# numitron-driver-v001.net
KiCad netlist of a schematic drawn in EAGLE
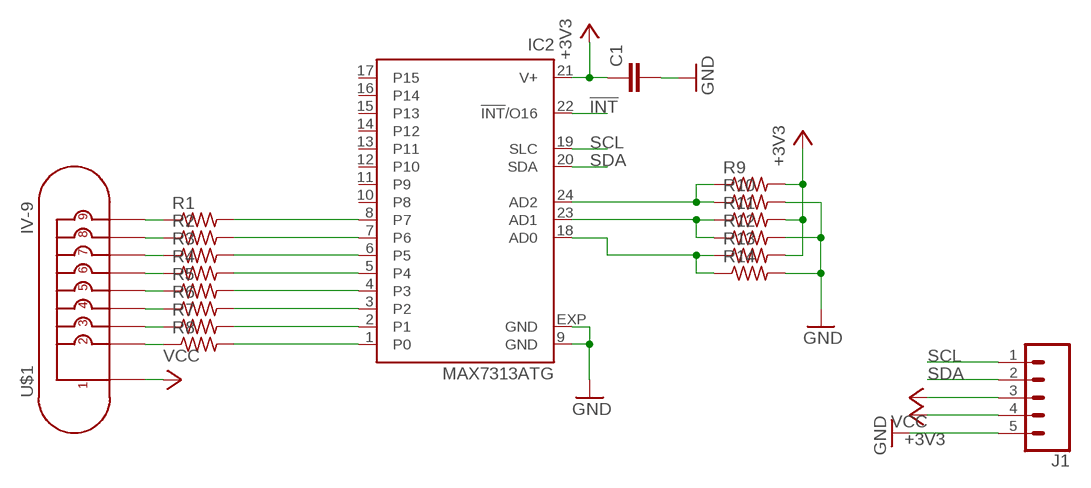
[diagram p0: schematic, sheet 1]

(export (version "E")
  (design (tool "Eeschema 10.0.6"))
  (components
    (comp (ref "C1")
      (value "C-EUC0603")
      (footprint "eagle-import:C0603")
      (libsource (lib "eagle-import") (part "C-EUC0603"))
    )
    (comp (ref "IC2")
      (value "MAX7313ATG")
      (footprint "eagle-import:TQFN24-EP")
      (fields (field (name "MF") "MAXIM"))
      (libsource (lib "eagle-import") (part "MAX7313ATG"))
    )
    (comp (ref "J1")
      (value "CONN_05NO_SILK")
      (footprint "eagle-import:1X05_NO_SILK")
      (libsource (lib "eagle-import") (part "CONN_05NO_SILK"))
    )
    (comp (ref "R1")
      (value "R-US_R0603")
      (footprint "eagle-import:R0603")
      (libsource (lib "eagle-import") (part "R-US_R0603"))
    )
    (comp (ref "R2")
      (value "R-US_R0603")
      (footprint "eagle-import:R0603")
      (libsource (lib "eagle-import") (part "R-US_R0603"))
    )
    (comp (ref "R3")
      (value "R-US_R0603")
      (footprint "eagle-import:R0603")
      (libsource (lib "eagle-import") (part "R-US_R0603"))
    )
    (comp (ref "R4")
      (value "R-US_R0603")
      (footprint "eagle-import:R0603")
      (libsource (lib "eagle-import") (part "R-US_R0603"))
    )
    (comp (ref "R5")
      (value "R-US_R0603")
      (footprint "eagle-import:R0603")
      (libsource (lib "eagle-import") (part "R-US_R0603"))
    )
    (comp (ref "R6")
      (value "R-US_R0603")
      (footprint "eagle-import:R0603")
      (libsource (lib "eagle-import") (part "R-US_R0603"))
    )
    (comp (ref "R7")
      (value "R-US_R0603")
      (footprint "eagle-import:R0603")
      (libsource (lib "eagle-import") (part "R-US_R0603"))
    )
    (comp (ref "R8")
      (value "R-US_R0603")
      (footprint "eagle-import:R0603")
      (libsource (lib "eagle-import") (part "R-US_R0603"))
    )
    (comp (ref "R9")
      (value "R-US_R0402")
      (footprint "eagle-import:R0402")
      (libsource (lib "eagle-import") (part "R-US_R0402"))
    )
    (comp (ref "R10")
      (value "R-US_R0402")
      (footprint "eagle-import:R0402")
      (libsource (lib "eagle-import") (part "R-US_R0402"))
    )
    (comp (ref "R11")
      (value "R-US_R0402")
      (footprint "eagle-import:R0402")
      (libsource (lib "eagle-import") (part "R-US_R0402"))
    )
    (comp (ref "R12")
      (value "R-US_R0402")
      (footprint "eagle-import:R0402")
      (libsource (lib "eagle-import") (part "R-US_R0402"))
    )
    (comp (ref "R13")
      (value "R-US_R0402")
      (footprint "eagle-import:R0402")
      (libsource (lib "eagle-import") (part "R-US_R0402"))
    )
    (comp (ref "R14")
      (value "R-US_R0402")
      (footprint "eagle-import:R0402")
      (libsource (lib "eagle-import") (part "R-US_R0402"))
    )
    (comp (ref "U$1")
      (value "IV-9")
      (footprint "eagle-import:IV-9")
      (libsource (lib "eagle-import") (part "IV-9"))
    )
  )
  (nets
    (net (code "1") (name "+3V3") (class "Default")
      (node (ref "C1") (pin "1") (pinfunction "1_1") (pintype "passive"))
      (node (ref "IC2") (pin "21") (pinfunction "V+_21") (pintype "power_in"))
      (node (ref "J1") (pin "4") (pinfunction "4_4") (pintype "passive"))
      (node (ref "R11") (pin "2") (pinfunction "2_2") (pintype "passive"))
      (node (ref "R13") (pin "2") (pinfunction "2_2") (pintype "passive"))
      (node (ref "R9") (pin "2") (pinfunction "2_2") (pintype "passive"))
    )
    (net (code "2") (name "/SCL") (class "Default")
      (node (ref "IC2") (pin "19") (pinfunction "SLC_19") (pintype "input"))
      (node (ref "J1") (pin "1") (pinfunction "1_1") (pintype "passive"))
    )
    (net (code "3") (name "/SDA") (class "Default")
      (node (ref "IC2") (pin "20") (pinfunction "SDA_20") (pintype "bidirectional"))
      (node (ref "J1") (pin "2") (pinfunction "2_2") (pintype "passive"))
    )
    (net (code "4") (name "/~{INT}") (class "Default")
      (node (ref "IC2") (pin "22") (pinfunction "~{INT}/O16_22") (pintype "open_collector"))
    )
    (net (code "5") (name "GND") (class "Default")
      (node (ref "C1") (pin "2") (pinfunction "2_2") (pintype "passive"))
      (node (ref "IC2") (pin "9") (pinfunction "GND_9") (pintype "power_in"))
      (node (ref "IC2") (pin "EXP") (pinfunction "GND_EXP") (pintype "power_in"))
      (node (ref "J1") (pin "5") (pinfunction "5_5") (pintype "passive"))
      (node (ref "R10") (pin "2") (pinfunction "2_2") (pintype "passive"))
      (node (ref "R12") (pin "2") (pinfunction "2_2") (pintype "passive"))
      (node (ref "R14") (pin "2") (pinfunction "2_2") (pintype "passive"))
    )
    (net (code "6") (name "Net-(IC2-AD0)") (class "Default")
      (node (ref "IC2") (pin "18") (pinfunction "AD0_18") (pintype "input"))
      (node (ref "R13") (pin "1") (pinfunction "1_1") (pintype "passive"))
      (node (ref "R14") (pin "1") (pinfunction "1_1") (pintype "passive"))
    )
    (net (code "7") (name "Net-(IC2-AD1)") (class "Default")
      (node (ref "IC2") (pin "23") (pinfunction "AD1_23") (pintype "input"))
      (node (ref "R11") (pin "1") (pinfunction "1_1") (pintype "passive"))
      (node (ref "R12") (pin "1") (pinfunction "1_1") (pintype "passive"))
    )
    (net (code "8") (name "Net-(IC2-AD2)") (class "Default")
      (node (ref "IC2") (pin "24") (pinfunction "AD2_24") (pintype "input"))
      (node (ref "R10") (pin "1") (pinfunction "1_1") (pintype "passive"))
      (node (ref "R9") (pin "1") (pinfunction "1_1") (pintype "passive"))
    )
    (net (code "9") (name "Net-(IC2-P0)") (class "Default")
      (node (ref "IC2") (pin "1") (pinfunction "P0_1") (pintype "bidirectional"))
      (node (ref "R8") (pin "2") (pinfunction "2_2") (pintype "passive"))
    )
    (net (code "10") (name "Net-(IC2-P1)") (class "Default")
      (node (ref "IC2") (pin "2") (pinfunction "P1_2") (pintype "bidirectional"))
      (node (ref "R7") (pin "2") (pinfunction "2_2") (pintype "passive"))
    )
    (net (code "11") (name "Net-(IC2-P2)") (class "Default")
      (node (ref "IC2") (pin "3") (pinfunction "P2_3") (pintype "bidirectional"))
      (node (ref "R6") (pin "2") (pinfunction "2_2") (pintype "passive"))
    )
    (net (code "12") (name "Net-(IC2-P3)") (class "Default")
      (node (ref "IC2") (pin "4") (pinfunction "P3_4") (pintype "bidirectional"))
      (node (ref "R5") (pin "2") (pinfunction "2_2") (pintype "passive"))
    )
    (net (code "13") (name "Net-(IC2-P4)") (class "Default")
      (node (ref "IC2") (pin "5") (pinfunction "P4_5") (pintype "bidirectional"))
      (node (ref "R4") (pin "2") (pinfunction "2_2") (pintype "passive"))
    )
    (net (code "14") (name "Net-(IC2-P5)") (class "Default")
      (node (ref "IC2") (pin "6") (pinfunction "P5_6") (pintype "bidirectional"))
      (node (ref "R3") (pin "2") (pinfunction "2_2") (pintype "passive"))
    )
    (net (code "15") (name "Net-(IC2-P6)") (class "Default")
      (node (ref "IC2") (pin "7") (pinfunction "P6_7") (pintype "bidirectional"))
      (node (ref "R2") (pin "2") (pinfunction "2_2") (pintype "passive"))
    )
    (net (code "16") (name "Net-(IC2-P7)") (class "Default")
      (node (ref "IC2") (pin "8") (pinfunction "P7_8") (pintype "bidirectional"))
      (node (ref "R1") (pin "2") (pinfunction "2_2") (pintype "passive"))
    )
    (net (code "17") (name "Net-(R1-Pad1)") (class "Default")
      (node (ref "R1") (pin "1") (pinfunction "1_1") (pintype "passive"))
      (node (ref "U$1") (pin "9") (pinfunction "9_9") (pintype "bidirectional"))
    )
    (net (code "18") (name "Net-(R2-Pad1)") (class "Default")
      (node (ref "R2") (pin "1") (pinfunction "1_1") (pintype "passive"))
      (node (ref "U$1") (pin "8") (pinfunction "8_8") (pintype "bidirectional"))
    )
    (net (code "19") (name "Net-(R3-Pad1)") (class "Default")
      (node (ref "R3") (pin "1") (pinfunction "1_1") (pintype "passive"))
      (node (ref "U$1") (pin "7") (pinfunction "7_7") (pintype "bidirectional"))
    )
    (net (code "20") (name "Net-(R4-Pad1)") (class "Default")
      (node (ref "R4") (pin "1") (pinfunction "1_1") (pintype "passive"))
      (node (ref "U$1") (pin "6") (pinfunction "6_6") (pintype "bidirectional"))
    )
    (net (code "21") (name "Net-(R5-Pad1)") (class "Default")
      (node (ref "R5") (pin "1") (pinfunction "1_1") (pintype "passive"))
      (node (ref "U$1") (pin "5") (pinfunction "5_5") (pintype "bidirectional"))
    )
    (net (code "22") (name "Net-(R6-Pad1)") (class "Default")
      (node (ref "R6") (pin "1") (pinfunction "1_1") (pintype "passive"))
      (node (ref "U$1") (pin "4") (pinfunction "4_4") (pintype "bidirectional"))
    )
    (net (code "23") (name "Net-(R7-Pad1)") (class "Default")
      (node (ref "R7") (pin "1") (pinfunction "1_1") (pintype "passive"))
      (node (ref "U$1") (pin "3") (pinfunction "3_3") (pintype "bidirectional"))
    )
    (net (code "24") (name "Net-(R8-Pad1)") (class "Default")
      (node (ref "R8") (pin "1") (pinfunction "1_1") (pintype "passive"))
      (node (ref "U$1") (pin "2") (pinfunction "2_2") (pintype "bidirectional"))
    )
    (net (code "25") (name "VCC") (class "Default")
      (node (ref "J1") (pin "3") (pinfunction "3_3") (pintype "passive"))
      (node (ref "U$1") (pin "1") (pinfunction "1_1") (pintype "bidirectional"))
    )
    (net (code "26") (name "unconnected-(IC2-P8-Pad10)") (class "Default")
      (node (ref "IC2") (pin "10") (pinfunction "P8_10") (pintype "bidirectional"))
    )
    (net (code "27") (name "unconnected-(IC2-P9-Pad11)") (class "Default")
      (node (ref "IC2") (pin "11") (pinfunction "P9_11") (pintype "bidirectional"))
    )
    (net (code "28") (name "unconnected-(IC2-P10-Pad12)") (class "Default")
      (node (ref "IC2") (pin "12") (pinfunction "P10_12") (pintype "bidirectional"))
    )
    (net (code "29") (name "unconnected-(IC2-P11-Pad13)") (class "Default")
      (node (ref "IC2") (pin "13") (pinfunction "P11_13") (pintype "bidirectional"))
    )
    (net (code "30") (name "unconnected-(IC2-P12-Pad14)") (class "Default")
      (node (ref "IC2") (pin "14") (pinfunction "P12_14") (pintype "bidirectional"))
    )
    (net (code "31") (name "unconnected-(IC2-P13-Pad15)") (class "Default")
      (node (ref "IC2") (pin "15") (pinfunction "P13_15") (pintype "bidirectional"))
    )
    (net (code "32") (name "unconnected-(IC2-P14-Pad16)") (class "Default")
      (node (ref "IC2") (pin "16") (pinfunction "P14_16") (pintype "bidirectional"))
    )
    (net (code "33") (name "unconnected-(IC2-P15-Pad17)") (class "Default")
      (node (ref "IC2") (pin "17") (pinfunction "P15_17") (pintype "bidirectional"))
    )
  )
)
